# design.net
KiCad netlist of a schematic drawn in Altium Designer
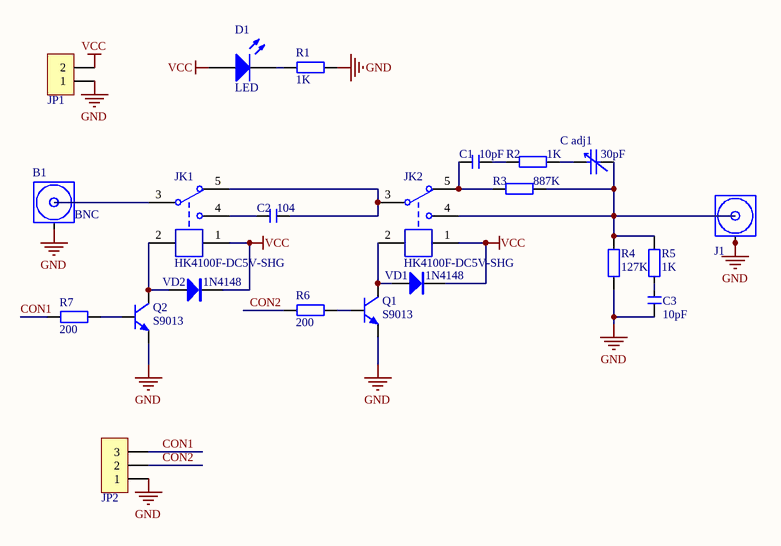
[diagram p0: 输入耦合衰减.SchDoc]

(export (version "E")
  (design (tool "Eeschema 10.0.6"))
  (components
    (comp (ref "B1")
      (value "BNC")
      (footprint "BNC")
      (description "BNC座子")
      (libsource (lib "LIB") (part "BNC"))
    )
    (comp (ref "C adj1")
      (value "30pF")
      (footprint "Cap adj")
      (fields (field (name "Comment") "C adj"))
      (libsource (lib "LIB") (part "Cap adj"))
    )
    (comp (ref "C1")
      (value "10pF")
      (footprint "C 0603")
      (description "无极性贴片电容")
      (fields (field (name "版权归属") "源创客"))
      (libsource (lib "电阻-电容-电感") (part "C"))
    )
    (comp (ref "C2")
      (value "104")
      (footprint "C 0805")
      (description "无极性贴片电容")
      (fields (field (name "版权归属") "源创客"))
      (libsource (lib "电阻-电容-电感") (part "C"))
    )
    (comp (ref "C3")
      (value "10pF")
      (footprint "C 0603")
      (description "无极性贴片电容")
      (fields (field (name "版权归属") "源创客"))
      (libsource (lib "电阻-电容-电感") (part "C"))
    )
    (comp (ref "D1")
      (value "LED")
      (footprint "LED_0805")
      (description "发光二极管")
      (fields (field (name "PUBLISHER") "Altium Limited"))
      (libsource (lib "LIB") (part "LED"))
    )
    (comp (ref "J1") (value "COAX") (footprint "MCX5.08-5-H") (libsource (lib "LIB") (part "COAX")))
    (comp (ref "JK1")
      (value "HK4100F-DC5V-SHG")
      (footprint "HK4100F")
      (description "单路双控继电器")
      (fields (field (name "版权归属") "源创客"))
      (libsource (lib "继电器") (part "HK4100F"))
    )
    (comp (ref "JK2")
      (value "HK4100F-DC5V-SHG")
      (footprint "HK4100F")
      (description "单路双控继电器")
      (fields (field (name "版权归属") "源创客"))
      (libsource (lib "继电器") (part "HK4100F"))
    )
    (comp (ref "JP1")
      (value "HDR-1X2")
      (footprint "XH2.54-2P_H")
      (description "2P接插件")
      (fields (field (name "版权归属") "源创客"))
      (libsource (lib "接插件") (part "Header 2"))
    )
    (comp (ref "JP2")
      (value "HDR-1X3")
      (footprint "HDR-1X3")
      (description "3P接插件")
      (fields (field (name "版权归属") "源创客"))
      (libsource (lib "接插件") (part "Header 3"))
    )
    (comp (ref "Q1")
      (value "S9013")
      (footprint "SOT23-3N")
      (description "低频放大-NPN型")
      (fields (field (name "版权归属") "源创客"))
      (libsource (lib "三极管") (part "9013-SMD"))
    )
    (comp (ref "Q2")
      (value "S9013")
      (footprint "SOT23-3N")
      (description "低频放大-NPN型")
      (fields (field (name "版权归属") "源创客"))
      (libsource (lib "三极管") (part "9013-SMD"))
    )
    (comp (ref "R1")
      (value "1K")
      (footprint "R 0805")
      (description "贴片电阻")
      (fields (field (name "版权归属") "源创客"))
      (libsource (lib "电阻-电容-电感") (part "R"))
    )
    (comp (ref "R2")
      (value "1K")
      (footprint "R 0603")
      (description "贴片电阻")
      (fields (field (name "版权归属") "源创客"))
      (libsource (lib "电阻-电容-电感") (part "R"))
    )
    (comp (ref "R3")
      (value "887K")
      (footprint "R 0603")
      (description "贴片电阻")
      (fields (field (name "版权归属") "源创客"))
      (libsource (lib "电阻-电容-电感") (part "R"))
    )
    (comp (ref "R4")
      (value "127K")
      (footprint "R 0603")
      (description "贴片电阻")
      (fields (field (name "版权归属") "源创客"))
      (libsource (lib "电阻-电容-电感") (part "R"))
    )
    (comp (ref "R5")
      (value "1K")
      (footprint "R 0603")
      (description "贴片电阻")
      (fields (field (name "版权归属") "源创客"))
      (libsource (lib "电阻-电容-电感") (part "R"))
    )
    (comp (ref "R6")
      (value "200")
      (footprint "R 0603")
      (description "贴片电阻")
      (fields (field (name "版权归属") "源创客"))
      (libsource (lib "电阻-电容-电感") (part "R"))
    )
    (comp (ref "R7")
      (value "200")
      (footprint "R 0603")
      (description "贴片电阻")
      (fields (field (name "版权归属") "源创客"))
      (libsource (lib "电阻-电容-电感") (part "R"))
    )
    (comp (ref "VD1")
      (value "1N4148")
      (footprint "SOD-323")
      (description "高速开关二极管")
      (fields (field (name "版权归属") "源创客"))
      (libsource (lib "二极管-整流桥") (part "1N4148"))
    )
    (comp (ref "VD2")
      (value "1N4148")
      (footprint "SOD-323")
      (description "高速开关二极管")
      (fields (field (name "版权归属") "源创客"))
      (libsource (lib "二极管-整流桥") (part "1N4148"))
    )
  )
  (nets
    (net (code "1") (name "/CON1") (class "Default")
      (node (ref "JP2") (pin "3") (pinfunction "3_3") (pintype "passive"))
      (node (ref "R7") (pin "1") (pinfunction "1_1") (pintype "passive"))
    )
    (net (code "2") (name "/CON2") (class "Default")
      (node (ref "JP2") (pin "2") (pinfunction "2_2") (pintype "passive"))
      (node (ref "R6") (pin "1") (pinfunction "1_1") (pintype "passive"))
    )
    (net (code "3") (name "GND") (class "Default")
      (node (ref "B1") (pin "2") (pinfunction "GND_2") (pintype "passive"))
      (node (ref "C3") (pin "1") (pinfunction "1_1") (pintype "passive"))
      (node (ref "J1") (pin "2") (pinfunction "GND_2") (pintype "passive"))
      (node (ref "J1") (pin "3") (pinfunction "GND_3") (pintype "passive"))
      (node (ref "J1") (pin "4") (pinfunction "GND_4") (pintype "passive"))
      (node (ref "J1") (pin "5") (pinfunction "GND_5") (pintype "passive"))
      (node (ref "JP1") (pin "1") (pinfunction "1_1") (pintype "passive"))
      (node (ref "JP2") (pin "1") (pinfunction "1_1") (pintype "passive"))
      (node (ref "Q1") (pin "2") (pinfunction "E_2") (pintype "passive"))
      (node (ref "Q2") (pin "2") (pinfunction "E_2") (pintype "passive"))
      (node (ref "R1") (pin "2") (pinfunction "2_2") (pintype "passive"))
      (node (ref "R4") (pin "1") (pinfunction "1_1") (pintype "passive"))
    )
    (net (code "4") (name "Net-(B1-Signal)") (class "Default")
      (node (ref "B1") (pin "1") (pinfunction "Signal_1") (pintype "passive"))
      (node (ref "JK1") (pin "3") (pinfunction "3_3") (pintype "passive"))
    )
    (net (code "5") (name "Net-(C adj1-Pad1)") (class "Default")
      (node (ref "C adj1") (pin "1") (pinfunction "1_1") (pintype "passive"))
      (node (ref "R2") (pin "2") (pinfunction "2_2") (pintype "passive"))
    )
    (net (code "6") (name "Net-(C1-Pad1)") (class "Default")
      (node (ref "C1") (pin "1") (pinfunction "1_1") (pintype "passive"))
      (node (ref "JK2") (pin "5") (pinfunction "5_5") (pintype "passive"))
      (node (ref "R3") (pin "1") (pinfunction "1_1") (pintype "passive"))
    )
    (net (code "7") (name "Net-(C1-Pad2)") (class "Default")
      (node (ref "C1") (pin "2") (pinfunction "2_2") (pintype "passive"))
      (node (ref "R2") (pin "1") (pinfunction "1_1") (pintype "passive"))
    )
    (net (code "8") (name "Net-(C2-Pad1)") (class "Default")
      (node (ref "C2") (pin "1") (pinfunction "1_1") (pintype "passive"))
      (node (ref "JK1") (pin "4") (pinfunction "4_4") (pintype "passive"))
    )
    (net (code "9") (name "Net-(C2-Pad2)") (class "Default")
      (node (ref "C2") (pin "2") (pinfunction "2_2") (pintype "passive"))
      (node (ref "JK1") (pin "5") (pinfunction "5_5") (pintype "passive"))
      (node (ref "JK2") (pin "3") (pinfunction "3_3") (pintype "passive"))
    )
    (net (code "10") (name "Net-(C3-Pad2)") (class "Default")
      (node (ref "C3") (pin "2") (pinfunction "2_2") (pintype "passive"))
      (node (ref "R5") (pin "1") (pinfunction "1_1") (pintype "passive"))
    )
    (net (code "11") (name "Net-(D1-K)") (class "Default")
      (node (ref "D1") (pin "2") (pinfunction "K_2") (pintype "passive"))
      (node (ref "R1") (pin "1") (pinfunction "1_1") (pintype "passive"))
    )
    (net (code "12") (name "Net-(J1-Signal)") (class "Default")
      (node (ref "C adj1") (pin "2") (pinfunction "2_2") (pintype "passive"))
      (node (ref "J1") (pin "1") (pinfunction "Signal_1") (pintype "passive"))
      (node (ref "JK2") (pin "4") (pinfunction "4_4") (pintype "passive"))
      (node (ref "R3") (pin "2") (pinfunction "2_2") (pintype "passive"))
      (node (ref "R4") (pin "2") (pinfunction "2_2") (pintype "passive"))
      (node (ref "R5") (pin "2") (pinfunction "2_2") (pintype "passive"))
    )
    (net (code "13") (name "Net-(Q1-B)") (class "Default")
      (node (ref "Q1") (pin "1") (pinfunction "B_1") (pintype "passive"))
      (node (ref "R6") (pin "2") (pinfunction "2_2") (pintype "passive"))
    )
    (net (code "14") (name "Net-(Q1-C)") (class "Default")
      (node (ref "JK2") (pin "2") (pinfunction "2_2") (pintype "passive"))
      (node (ref "Q1") (pin "3") (pinfunction "C_3") (pintype "passive"))
      (node (ref "VD1") (pin "1") (pinfunction "A_1") (pintype "passive"))
    )
    (net (code "15") (name "Net-(Q2-B)") (class "Default")
      (node (ref "Q2") (pin "1") (pinfunction "B_1") (pintype "passive"))
      (node (ref "R7") (pin "2") (pinfunction "2_2") (pintype "passive"))
    )
    (net (code "16") (name "Net-(Q2-C)") (class "Default")
      (node (ref "JK1") (pin "2") (pinfunction "2_2") (pintype "passive"))
      (node (ref "Q2") (pin "3") (pinfunction "C_3") (pintype "passive"))
      (node (ref "VD2") (pin "1") (pinfunction "A_1") (pintype "passive"))
    )
    (net (code "17") (name "VCC") (class "Default")
      (node (ref "D1") (pin "1") (pinfunction "A_1") (pintype "passive"))
      (node (ref "JK1") (pin "1") (pinfunction "1_1") (pintype "passive"))
      (node (ref "JK2") (pin "1") (pinfunction "1_1") (pintype "passive"))
      (node (ref "JP1") (pin "2") (pinfunction "2_2") (pintype "passive"))
      (node (ref "VD1") (pin "2") (pinfunction "K_2") (pintype "passive"))
      (node (ref "VD2") (pin "2") (pinfunction "K_2") (pintype "passive"))
    )
  )
)
